# flood_sensor.net
KiCad netlist of a schematic drawn in EAGLE
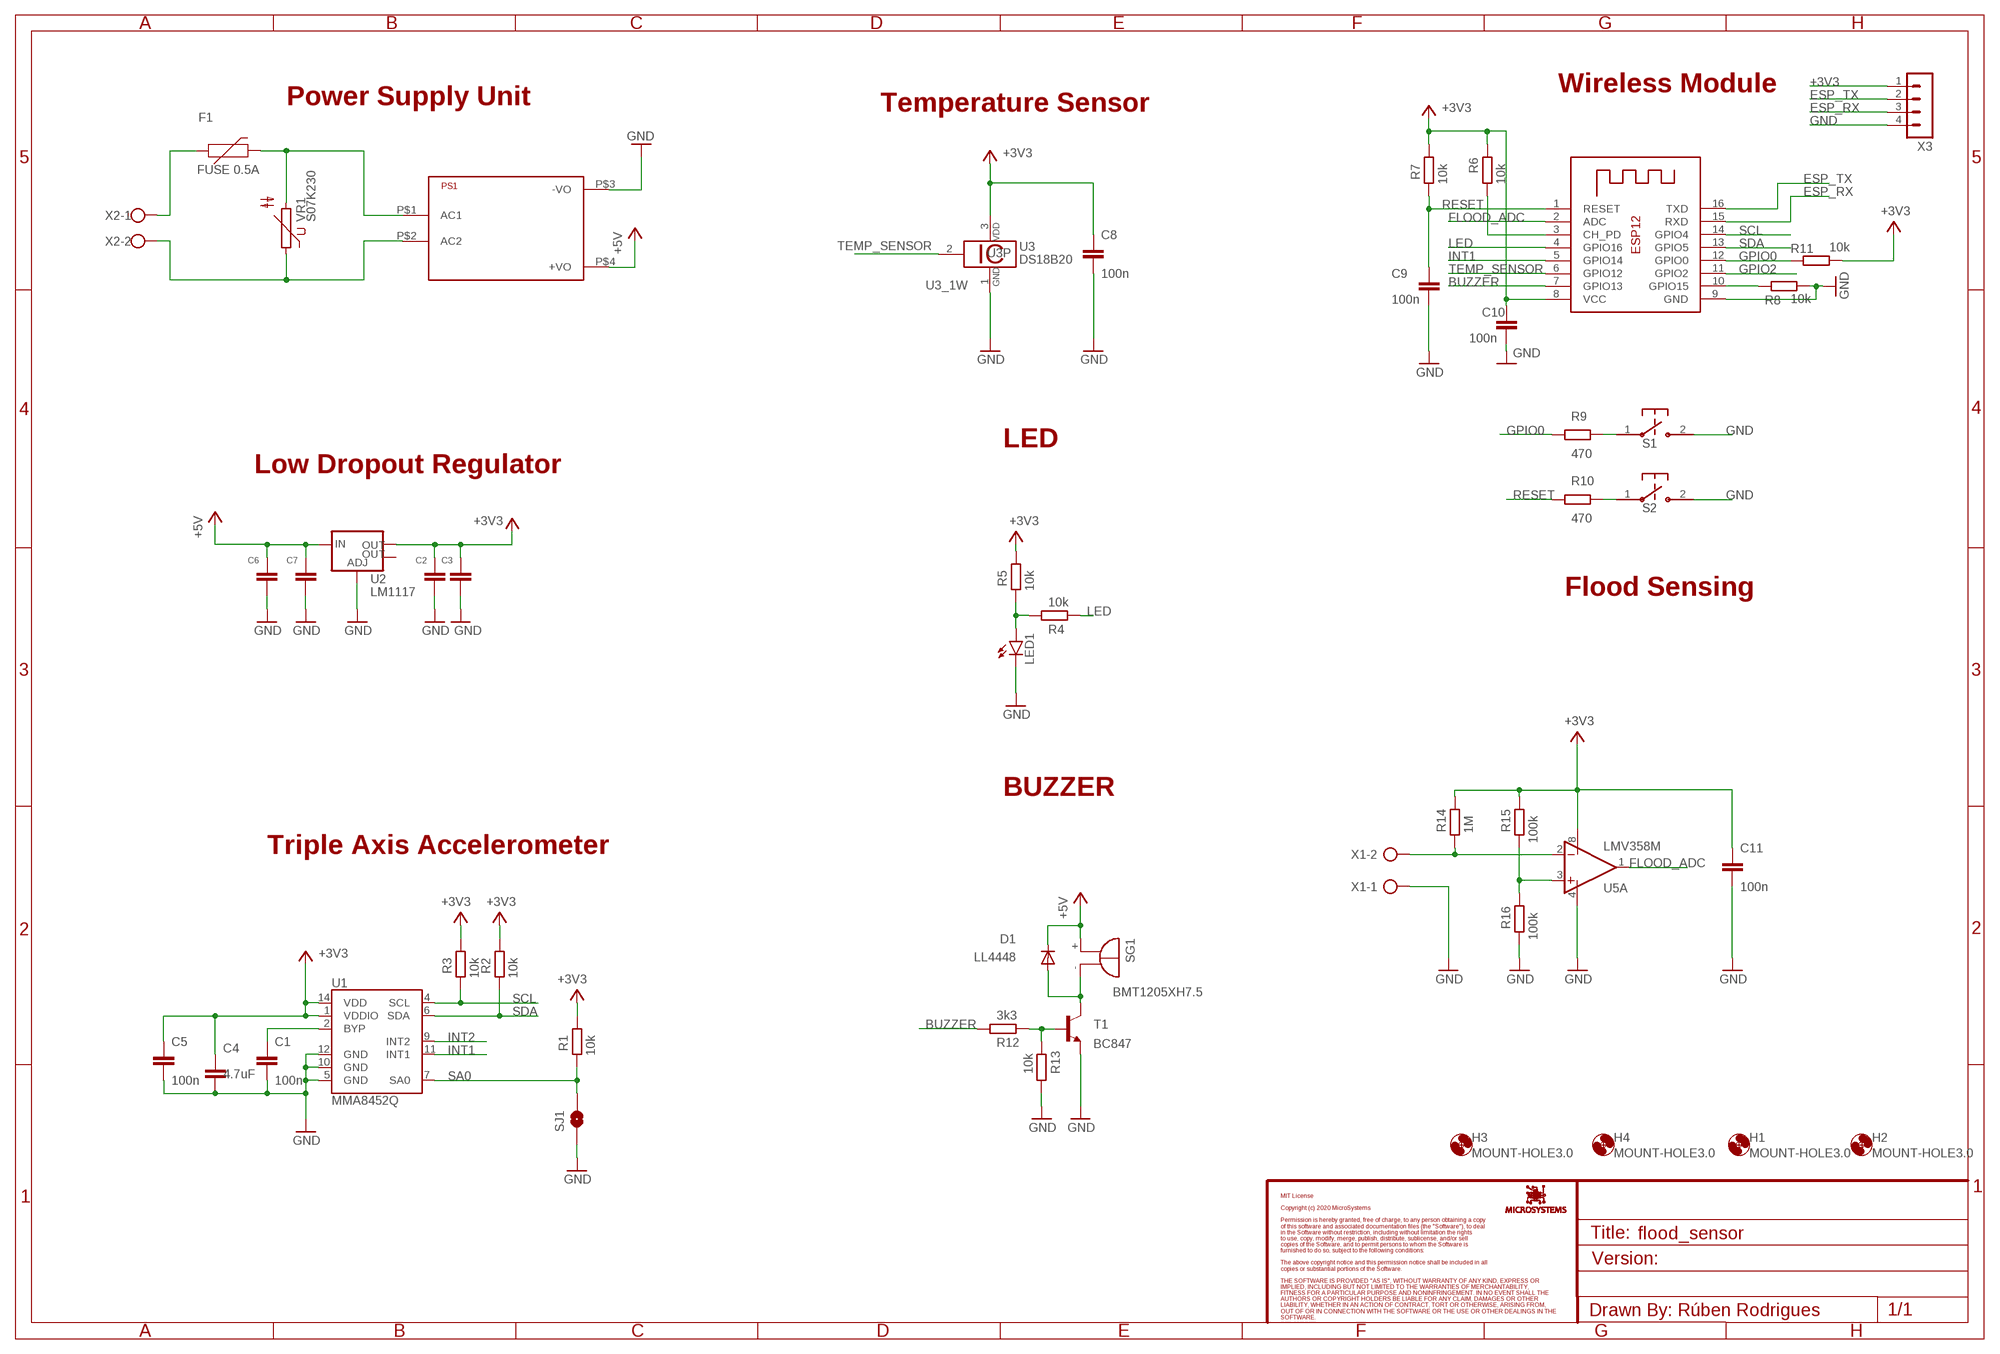
[diagram p0: schematic, sheet 1]

(export (version "E")
  (design (tool "Eeschema 10.0.6"))
  (components
    (comp (ref "C1")
      (value "100n")
      (footprint "eagle-import:C0805")
      (libsource (lib "eagle-import") (part "C-EUC0805"))
    )
    (comp (ref "C2")
      (value "100uF")
      (footprint "eagle-import:C1206")
      (libsource (lib "eagle-import") (part "rcl_334_C-EUC1206"))
    )
    (comp (ref "C3")
      (value "22uF")
      (footprint "eagle-import:C1206")
      (libsource (lib "eagle-import") (part "rcl_334_C-EUC1206"))
    )
    (comp (ref "C4")
      (value "4.7uF")
      (footprint "eagle-import:C0805")
      (libsource (lib "eagle-import") (part "rcl_334_C-EUC0805"))
    )
    (comp (ref "C5")
      (value "100n")
      (footprint "eagle-import:C0805")
      (libsource (lib "eagle-import") (part "rcl_334_C-EUC0805"))
    )
    (comp (ref "C6")
      (value "22uF")
      (footprint "eagle-import:C1206")
      (libsource (lib "eagle-import") (part "rcl_334_C-EUC1206"))
    )
    (comp (ref "C7")
      (value "100uF")
      (footprint "eagle-import:C1206")
      (libsource (lib "eagle-import") (part "rcl_334_C-EUC1206"))
    )
    (comp (ref "C8")
      (value "100n")
      (footprint "eagle-import:C0805")
      (libsource (lib "eagle-import") (part "rcl_334_C-EUC0805"))
    )
    (comp (ref "C9")
      (value "100n")
      (footprint "eagle-import:C0805")
      (libsource (lib "eagle-import") (part "C-EUC0805"))
    )
    (comp (ref "C10")
      (value "100n")
      (footprint "eagle-import:C0805")
      (libsource (lib "eagle-import") (part "C-EUC0805"))
    )
    (comp (ref "C11")
      (value "100n")
      (footprint "eagle-import:C0805")
      (libsource (lib "eagle-import") (part "rcl_334_C-EUC0805"))
    )
    (comp (ref "D1")
      (value "LL4448")
      (footprint "eagle-import:SOD80C")
      (libsource (lib "eagle-import") (part "DIODE-SOD80C"))
    )
    (comp (ref "F1")
      (value "FUSE 0.5A")
      (footprint "eagle-import:PTH")
      (libsource (lib "eagle-import") (part "PPTC_PTH"))
    )
    (comp (ref "H1")
      (value "MOUNT-HOLE3.0")
      (footprint "eagle-import:3,0")
      (libsource (lib "eagle-import") (part "MOUNT-HOLE3.0"))
    )
    (comp (ref "H2")
      (value "MOUNT-HOLE3.0")
      (footprint "eagle-import:3,0")
      (libsource (lib "eagle-import") (part "MOUNT-HOLE3.0"))
    )
    (comp (ref "H3")
      (value "MOUNT-HOLE3.0")
      (footprint "eagle-import:3,0")
      (libsource (lib "eagle-import") (part "MOUNT-HOLE3.0"))
    )
    (comp (ref "H4")
      (value "MOUNT-HOLE3.0")
      (footprint "eagle-import:3,0")
      (libsource (lib "eagle-import") (part "MOUNT-HOLE3.0"))
    )
    (comp (ref "LED1")
      (value "LED3MM")
      (footprint "eagle-import:LED3MM")
      (libsource (lib "eagle-import") (part "LED3MM"))
    )
    (comp (ref "PS1")
      (value "HLK-PM013W")
      (footprint "eagle-import:HLK-PM01")
      (libsource (lib "eagle-import") (part "HLK-PM013W"))
    )
    (comp (ref "R1")
      (value "10k")
      (footprint "eagle-import:R0805")
      (libsource (lib "eagle-import") (part "R-EU_R0805"))
    )
    (comp (ref "R2")
      (value "10k")
      (footprint "eagle-import:R0805")
      (libsource (lib "eagle-import") (part "R-EU_R0805"))
    )
    (comp (ref "R3")
      (value "10k")
      (footprint "eagle-import:R0805")
      (libsource (lib "eagle-import") (part "R-EU_R0805"))
    )
    (comp (ref "R4")
      (value "10k")
      (footprint "eagle-import:R0805")
      (libsource (lib "eagle-import") (part "R-EU_R0805"))
    )
    (comp (ref "R5")
      (value "10k")
      (footprint "eagle-import:R0805")
      (libsource (lib "eagle-import") (part "R-EU_R0805"))
    )
    (comp (ref "R6")
      (value "10k")
      (footprint "eagle-import:R0805")
      (libsource (lib "eagle-import") (part "R-EU_R0805"))
    )
    (comp (ref "R7")
      (value "10k")
      (footprint "eagle-import:R0805")
      (libsource (lib "eagle-import") (part "R-EU_R0805"))
    )
    (comp (ref "R8")
      (value "10k")
      (footprint "eagle-import:R0805")
      (libsource (lib "eagle-import") (part "R-EU_R0805"))
    )
    (comp (ref "R9")
      (value "470")
      (footprint "eagle-import:R0805")
      (libsource (lib "eagle-import") (part "R-EU_R0805"))
    )
    (comp (ref "R10")
      (value "470")
      (footprint "eagle-import:R0805")
      (libsource (lib "eagle-import") (part "R-EU_R0805"))
    )
    (comp (ref "R11")
      (value "10k")
      (footprint "eagle-import:R0805")
      (libsource (lib "eagle-import") (part "R-EU_R0805"))
    )
    (comp (ref "R12")
      (value "3k3")
      (footprint "eagle-import:R0805")
      (libsource (lib "eagle-import") (part "R-EU_R0805"))
    )
    (comp (ref "R13")
      (value "10k")
      (footprint "eagle-import:R0805")
      (libsource (lib "eagle-import") (part "R-EU_R0805"))
    )
    (comp (ref "R14")
      (value "1M")
      (footprint "eagle-import:R0805")
      (libsource (lib "eagle-import") (part "R-EU_R0805"))
    )
    (comp (ref "R15")
      (value "100k")
      (footprint "eagle-import:R0805")
      (libsource (lib "eagle-import") (part "R-EU_R0805"))
    )
    (comp (ref "R16")
      (value "100k")
      (footprint "eagle-import:R0805")
      (libsource (lib "eagle-import") (part "R-EU_R0805"))
    )
    (comp (ref "S1")
      (value "SWITCHES_B3U-1000P")
      (footprint "eagle-import:SWITCHES_B3U-1000P")
      (fields (field (name "MANUFACTURER") "Omron") (field (name "MPN") "B3U-1000P"))
      (libsource (lib "eagle-import") (part "SWITCHES_B3U-1000P"))
    )
    (comp (ref "S2")
      (value "SWITCHES_B3U-1000P")
      (footprint "eagle-import:SWITCHES_B3U-1000P")
      (fields (field (name "MANUFACTURER") "Omron") (field (name "MPN") "B3U-1000P"))
      (libsource (lib "eagle-import") (part "SWITCHES_B3U-1000P"))
    )
    (comp (ref "SG1")
      (value "BMT1205XH7.5")
      (footprint "eagle-import:BMT1205XH7.5")
      (libsource (lib "eagle-import") (part "BMT1205XH7.5"))
    )
    (comp (ref "SJ1")
      (value "SOLDERJUMPERNO")
      (footprint "eagle-import:SJ_2S-NO")
      (libsource (lib "eagle-import") (part "SOLDERJUMPERNO"))
    )
    (comp (ref "T1")
      (value "BC847")
      (footprint "eagle-import:SOT23")
      (libsource (lib "eagle-import") (part "BC847"))
    )
    (comp (ref "U1")
      (value "MMA8452Q")
      (footprint "eagle-import:QFN-16_0.5MM")
      (libsource (lib "eagle-import") (part "MMA8452Q"))
    )
    (comp (ref "U2")
      (value "LM1117")
      (footprint "eagle-import:SOT223")
      (libsource (lib "eagle-import") (part "V_REG_LM1117SOT223"))
    )
    (comp (ref "U3")
      (value "DS18B20")
      (footprint "eagle-import:TO92-")
      (libsource (lib "eagle-import") (part "DS18B20"))
    )
    (comp (ref "U4")
      (value "ESP-12")
      (footprint "eagle-import:ESP-12")
      (libsource (lib "eagle-import") (part "ESP-12"))
    )
    (comp (ref "U5")
      (value "LMV358M")
      (footprint "eagle-import:SO08")
      (libsource (lib "eagle-import") (part "LMV358?M"))
    )
    (comp (ref "VR1")
      (value "S07K230")
      (footprint "eagle-import:S07K230")
      (libsource (lib "eagle-import") (part "S07K230"))
    )
    (comp (ref "X1")
      (value "W237-102")
      (footprint "eagle-import:W237-102")
      (fields (field (name "MPN") "237-102"))
      (libsource (lib "eagle-import") (part "W237-102"))
    )
    (comp (ref "X2")
      (value "W237-102")
      (footprint "eagle-import:W237-102")
      (fields (field (name "MPN") "237-102"))
      (libsource (lib "eagle-import") (part "W237-102"))
    )
    (comp (ref "X3")
      (value "MA04-1")
      (footprint "eagle-import:MA04-1")
      (libsource (lib "eagle-import") (part "MA04-1"))
    )
  )
  (nets
    (net (code "1") (name "+3V3") (class "Default")
      (node (ref "C10") (pin "1") (pinfunction "1_1") (pintype "passive"))
      (node (ref "C11") (pin "1") (pinfunction "1_1") (pintype "passive"))
      (node (ref "C2") (pin "1") (pinfunction "1_1") (pintype "passive"))
      (node (ref "C3") (pin "1") (pinfunction "1_1") (pintype "passive"))
      (node (ref "C4") (pin "1") (pinfunction "1_1") (pintype "passive"))
      (node (ref "C5") (pin "1") (pinfunction "1_1") (pintype "passive"))
      (node (ref "C8") (pin "1") (pinfunction "1_1") (pintype "passive"))
      (node (ref "R1") (pin "1") (pinfunction "1_1") (pintype "passive"))
      (node (ref "R11") (pin "2") (pinfunction "2_2") (pintype "passive"))
      (node (ref "R14") (pin "1") (pinfunction "1_1") (pintype "passive"))
      (node (ref "R15") (pin "1") (pinfunction "1_1") (pintype "passive"))
      (node (ref "R2") (pin "1") (pinfunction "1_1") (pintype "passive"))
      (node (ref "R3") (pin "1") (pinfunction "1_1") (pintype "passive"))
      (node (ref "R5") (pin "1") (pinfunction "1_1") (pintype "passive"))
      (node (ref "R6") (pin "1") (pinfunction "1_1") (pintype "passive"))
      (node (ref "R7") (pin "1") (pinfunction "1_1") (pintype "passive"))
      (node (ref "U1") (pin "1") (pinfunction "VDDIO_1") (pintype "bidirectional"))
      (node (ref "U1") (pin "14") (pinfunction "VDD_14") (pintype "bidirectional"))
      (node (ref "U2") (pin "2") (pinfunction "OUT_2") (pintype "output"))
      (node (ref "U3") (pin "3") (pinfunction "VDD_3") (pintype "power_in"))
      (node (ref "U4") (pin "8") (pinfunction "VCC_8") (pintype "power_in"))
      (node (ref "U5") (pin "8") (pinfunction "V+_8") (pintype "power_in"))
      (node (ref "X3") (pin "1") (pinfunction "1_1") (pintype "passive"))
    )
    (net (code "2") (name "+5V") (class "Default")
      (node (ref "C6") (pin "1") (pinfunction "1_1") (pintype "passive"))
      (node (ref "C7") (pin "1") (pinfunction "1_1") (pintype "passive"))
      (node (ref "D1") (pin "C") (pinfunction "C_C") (pintype "passive"))
      (node (ref "PS1") (pin "P$4") (pinfunction "+VO_P$4") (pintype "bidirectional"))
      (node (ref "SG1") (pin "+") (pinfunction "+_+") (pintype "passive"))
      (node (ref "U2") (pin "3") (pinfunction "IN_3") (pintype "input"))
    )
    (net (code "3") (name "/BUZZER") (class "Default")
      (node (ref "R12") (pin "1") (pinfunction "1_1") (pintype "passive"))
      (node (ref "U4") (pin "7") (pinfunction "GPIO13_7") (pintype "bidirectional"))
    )
    (net (code "4") (name "/ESP_RX") (class "Default")
      (node (ref "U4") (pin "15") (pinfunction "RXD_15") (pintype "input"))
      (node (ref "X3") (pin "3") (pinfunction "3_3") (pintype "passive"))
    )
    (net (code "5") (name "/ESP_TX") (class "Default")
      (node (ref "U4") (pin "16") (pinfunction "TXD_16") (pintype "output"))
      (node (ref "X3") (pin "2") (pinfunction "2_2") (pintype "passive"))
    )
    (net (code "6") (name "/FLOOD_ADC") (class "Default")
      (node (ref "U4") (pin "2") (pinfunction "ADC_2") (pintype "passive"))
      (node (ref "U5") (pin "1") (pinfunction "OUT_1") (pintype "output"))
    )
    (net (code "7") (name "/GPIO0") (class "Default")
      (node (ref "R11") (pin "1") (pinfunction "1_1") (pintype "passive"))
      (node (ref "R9") (pin "1") (pinfunction "1_1") (pintype "passive"))
      (node (ref "U4") (pin "12") (pinfunction "GPIO0_12") (pintype "bidirectional"))
    )
    (net (code "8") (name "/GPIO2") (class "Default")
      (node (ref "U4") (pin "11") (pinfunction "GPIO2_11") (pintype "bidirectional"))
    )
    (net (code "9") (name "/INT1") (class "Default")
      (node (ref "U1") (pin "11") (pinfunction "INT1_11") (pintype "bidirectional"))
      (node (ref "U4") (pin "5") (pinfunction "GPIO14_5") (pintype "bidirectional"))
    )
    (net (code "10") (name "/INT2") (class "Default")
      (node (ref "U1") (pin "9") (pinfunction "INT2_9") (pintype "bidirectional"))
    )
    (net (code "11") (name "/LED") (class "Default")
      (node (ref "R4") (pin "2") (pinfunction "2_2") (pintype "passive"))
      (node (ref "U4") (pin "4") (pinfunction "GPIO16_4") (pintype "bidirectional"))
    )
    (net (code "12") (name "/RESET") (class "Default")
      (node (ref "C9") (pin "1") (pinfunction "1_1") (pintype "passive"))
      (node (ref "R10") (pin "1") (pinfunction "1_1") (pintype "passive"))
      (node (ref "R7") (pin "2") (pinfunction "2_2") (pintype "passive"))
      (node (ref "U4") (pin "1") (pinfunction "RESET_1") (pintype "input"))
    )
    (net (code "13") (name "/SA0") (class "Default")
      (node (ref "R1") (pin "2") (pinfunction "2_2") (pintype "passive"))
      (node (ref "SJ1") (pin "2") (pinfunction "2_2") (pintype "passive"))
      (node (ref "U1") (pin "7") (pinfunction "SA0_7") (pintype "bidirectional"))
    )
    (net (code "14") (name "/SCL") (class "Default")
      (node (ref "R3") (pin "2") (pinfunction "2_2") (pintype "passive"))
      (node (ref "U1") (pin "4") (pinfunction "SCL_4") (pintype "bidirectional"))
      (node (ref "U4") (pin "14") (pinfunction "GPIO4_14") (pintype "bidirectional"))
    )
    (net (code "15") (name "/SDA") (class "Default")
      (node (ref "R2") (pin "2") (pinfunction "2_2") (pintype "passive"))
      (node (ref "U1") (pin "6") (pinfunction "SDA_6") (pintype "bidirectional"))
      (node (ref "U4") (pin "13") (pinfunction "GPIO5_13") (pintype "bidirectional"))
    )
    (net (code "16") (name "/TEMP_SENSOR") (class "Default")
      (node (ref "U3") (pin "2") (pinfunction "1W_2") (pintype "power_in"))
      (node (ref "U4") (pin "6") (pinfunction "GPIO12_6") (pintype "bidirectional"))
    )
    (net (code "17") (name "GND") (class "Default")
      (node (ref "C1") (pin "2") (pinfunction "2_2") (pintype "passive"))
      (node (ref "C10") (pin "2") (pinfunction "2_2") (pintype "passive"))
      (node (ref "C11") (pin "2") (pinfunction "2_2") (pintype "passive"))
      (node (ref "C2") (pin "2") (pinfunction "2_2") (pintype "passive"))
      (node (ref "C3") (pin "2") (pinfunction "2_2") (pintype "passive"))
      (node (ref "C4") (pin "2") (pinfunction "2_2") (pintype "passive"))
      (node (ref "C5") (pin "2") (pinfunction "2_2") (pintype "passive"))
      (node (ref "C6") (pin "2") (pinfunction "2_2") (pintype "passive"))
      (node (ref "C7") (pin "2") (pinfunction "2_2") (pintype "passive"))
      (node (ref "C8") (pin "2") (pinfunction "2_2") (pintype "passive"))
      (node (ref "C9") (pin "2") (pinfunction "2_2") (pintype "passive"))
      (node (ref "LED1") (pin "K") (pinfunction "C_K") (pintype "passive"))
      (node (ref "PS1") (pin "P$3") (pinfunction "-VO_P$3") (pintype "bidirectional"))
      (node (ref "R13") (pin "1") (pinfunction "1_1") (pintype "passive"))
      (node (ref "R16") (pin "2") (pinfunction "2_2") (pintype "passive"))
      (node (ref "R8") (pin "2") (pinfunction "2_2") (pintype "passive"))
      (node (ref "S1") (pin "2") (pinfunction "P$2_2") (pintype "passive"))
      (node (ref "S2") (pin "2") (pinfunction "P$2_2") (pintype "passive"))
      (node (ref "SJ1") (pin "1") (pinfunction "1_1") (pintype "passive"))
      (node (ref "T1") (pin "2") (pinfunction "E_2") (pintype "passive"))
      (node (ref "U1") (pin "10") (pinfunction "GND_10") (pintype "bidirectional"))
      (node (ref "U1") (pin "12") (pinfunction "GND_12") (pintype "bidirectional"))
      (node (ref "U1") (pin "5") (pinfunction "GND_5") (pintype "bidirectional"))
      (node (ref "U2") (pin "1") (pinfunction "ADJ_1") (pintype "input"))
      (node (ref "U3") (pin "1") (pinfunction "GND_1") (pintype "power_in"))
      (node (ref "U4") (pin "9") (pinfunction "GND_9") (pintype "power_in"))
      (node (ref "U5") (pin "4") (pinfunction "V-_4") (pintype "power_in"))
      (node (ref "X1") (pin "1") (pinfunction "KL_1") (pintype "passive"))
      (node (ref "X3") (pin "4") (pinfunction "4_4") (pintype "passive"))
    )
    (net (code "18") (name "Net-(F1-1)") (class "Default")
      (node (ref "F1") (pin "P$1") (pinfunction "1_P$1") (pintype "bidirectional"))
      (node (ref "X2") (pin "1") (pinfunction "KL_1") (pintype "passive"))
    )
    (net (code "19") (name "Net-(F1-2)") (class "Default")
      (node (ref "F1") (pin "P$2") (pinfunction "2_P$2") (pintype "bidirectional"))
      (node (ref "PS1") (pin "P$1") (pinfunction "AC1_P$1") (pintype "bidirectional"))
      (node (ref "VR1") (pin "2") (pinfunction "2_2") (pintype "passive"))
    )
    (net (code "20") (name "Net-(LED1-PadA)") (class "Default")
      (node (ref "LED1") (pin "A") (pinfunction "A_A") (pintype "passive"))
      (node (ref "R4") (pin "1") (pinfunction "1_1") (pintype "passive"))
      (node (ref "R5") (pin "2") (pinfunction "2_2") (pintype "passive"))
    )
    (net (code "21") (name "Net-(PS1-AC2)") (class "Default")
      (node (ref "PS1") (pin "P$2") (pinfunction "AC2_P$2") (pintype "bidirectional"))
      (node (ref "VR1") (pin "1") (pinfunction "1_1") (pintype "passive"))
      (node (ref "X2") (pin "2") (pinfunction "KL_2") (pintype "passive"))
    )
    (net (code "22") (name "Net-(S1-P$1)") (class "Default")
      (node (ref "R9") (pin "2") (pinfunction "2_2") (pintype "passive"))
      (node (ref "S1") (pin "1") (pinfunction "P$1_1") (pintype "passive"))
    )
    (net (code "23") (name "Net-(S2-P$1)") (class "Default")
      (node (ref "R10") (pin "2") (pinfunction "2_2") (pintype "passive"))
      (node (ref "S2") (pin "1") (pinfunction "P$1_1") (pintype "passive"))
    )
    (net (code "24") (name "Net-(T1-B)") (class "Default")
      (node (ref "R12") (pin "2") (pinfunction "2_2") (pintype "passive"))
      (node (ref "R13") (pin "2") (pinfunction "2_2") (pintype "passive"))
      (node (ref "T1") (pin "1") (pinfunction "B_1") (pintype "passive"))
    )
    (net (code "25") (name "Net-(T1-C)") (class "Default")
      (node (ref "D1") (pin "A") (pinfunction "A_A") (pintype "passive"))
      (node (ref "SG1") (pin "-") (pinfunction "-_-") (pintype "passive"))
      (node (ref "T1") (pin "3") (pinfunction "C_3") (pintype "passive"))
    )
    (net (code "26") (name "Net-(U1-BYP)") (class "Default")
      (node (ref "C1") (pin "1") (pinfunction "1_1") (pintype "passive"))
      (node (ref "U1") (pin "2") (pinfunction "BYP_2") (pintype "bidirectional"))
    )
    (net (code "27") (name "Net-(U4-CH_PD)") (class "Default")
      (node (ref "R6") (pin "2") (pinfunction "2_2") (pintype "passive"))
      (node (ref "U4") (pin "3") (pinfunction "CH_PD_3") (pintype "input"))
    )
    (net (code "28") (name "Net-(U4-GPIO15)") (class "Default")
      (node (ref "R8") (pin "1") (pinfunction "1_1") (pintype "passive"))
      (node (ref "U4") (pin "10") (pinfunction "GPIO15_10") (pintype "bidirectional"))
    )
    (net (code "29") (name "Net-(U5A-+IN)") (class "Default")
      (node (ref "R15") (pin "2") (pinfunction "2_2") (pintype "passive"))
      (node (ref "R16") (pin "1") (pinfunction "1_1") (pintype "passive"))
      (node (ref "U5") (pin "3") (pinfunction "+IN_3") (pintype "input"))
    )
    (net (code "30") (name "Net-(U5A--IN)") (class "Default")
      (node (ref "R14") (pin "2") (pinfunction "2_2") (pintype "passive"))
      (node (ref "U5") (pin "2") (pinfunction "-IN_2") (pintype "input"))
      (node (ref "X1") (pin "2") (pinfunction "KL_2") (pintype "passive"))
    )
    (net (code "31") (name "unconnected-(U2-OUT-Pad4)") (class "Default")
      (node (ref "U2") (pin "4") (pinfunction "OUT_4") (pintype "output"))
    )
  )
)
